# ESP_programmer_QFN_2.net
KiCad netlist of a schematic drawn in EAGLE
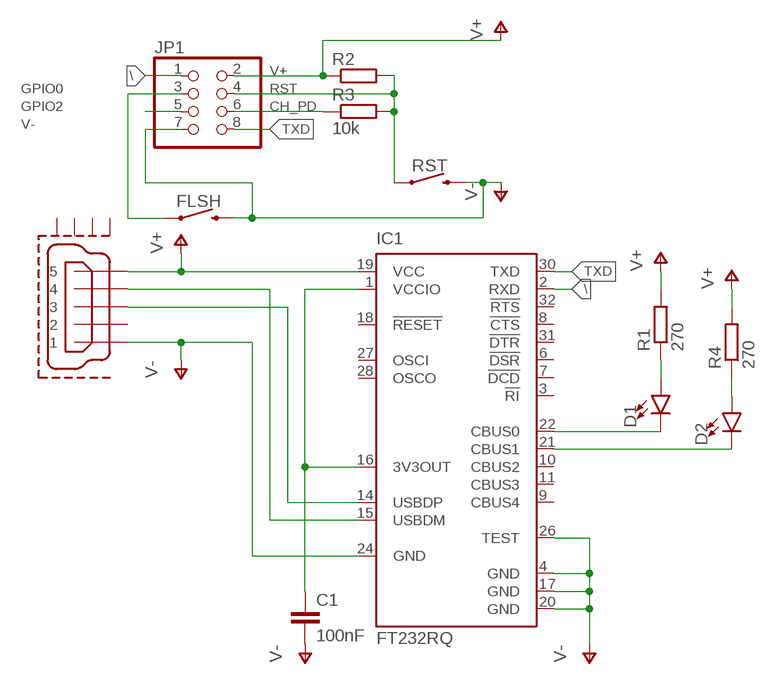
[diagram p0: schematic, sheet 1]

(export (version "E")
  (design (tool "Eeschema 10.0.6"))
  (components
    (comp (ref "C1")
      (value "100nF")
      (footprint "eagle-import:C1608")
      (libsource (lib "eagle-import") (part "C-EUC1608"))
    )
    (comp (ref "D1")
      (value "TX")
      (footprint "eagle-import:LED-0603")
      (libsource (lib "eagle-import") (part "LED-BLUE0603"))
    )
    (comp (ref "D2")
      (value "RX")
      (footprint "eagle-import:LED-0603")
      (libsource (lib "eagle-import") (part "LED-BLUE0603"))
    )
    (comp (ref "FLSH")
      (value "MOMENTARY-SWITCH-SPST-SMD-5.2-REDUNDANT")
      (footprint "eagle-import:TACTILE_SWITCH_SMD_5.2MM")
      (libsource (lib "eagle-import") (part "MOMENTARY-SWITCH-SPST-SMD-5.2-REDUNDANT"))
    )
    (comp (ref "IC1")
      (value "FT232RQ")
      (footprint "eagle-import:QFN32")
      (libsource (lib "eagle-import") (part "FT232RQ"))
    )
    (comp (ref "JP1")
      (value "PINHD-2X4")
      (footprint "eagle-import:2X04")
      (libsource (lib "eagle-import") (part "PINHD-2X4"))
    )
    (comp (ref "R1")
      (value "270")
      (footprint "eagle-import:R2012")
      (libsource (lib "eagle-import") (part "RR2012"))
    )
    (comp (ref "R2")
      (value "10k")
      (footprint "eagle-import:R2012")
      (libsource (lib "eagle-import") (part "RR2012"))
    )
    (comp (ref "R3")
      (value "10k")
      (footprint "eagle-import:R2012")
      (libsource (lib "eagle-import") (part "RR2012"))
    )
    (comp (ref "R4")
      (value "270")
      (footprint "eagle-import:R2012")
      (libsource (lib "eagle-import") (part "RR2012"))
    )
    (comp (ref "RST")
      (value "MOMENTARY-SWITCH-SPST-SMD-5.2-REDUNDANT")
      (footprint "eagle-import:TACTILE_SWITCH_SMD_5.2MM")
      (libsource (lib "eagle-import") (part "MOMENTARY-SWITCH-SPST-SMD-5.2-REDUNDANT"))
    )
    (comp (ref "U1")
      (value "MICRO-USB-RECEPTACLE47589-0001")
      (footprint "eagle-import:47589-0001")
      (libsource (lib "eagle-import") (part "MICRO-USB-RECEPTACLE47589-0001"))
    )
  )
  (nets
    (net (code "1") (name "/CH_PD") (class "Default")
      (node (ref "JP1") (pin "6") (pinfunction "6_6") (pintype "passive"))
      (node (ref "R3") (pin "1") (pinfunction "1_1") (pintype "passive"))
    )
    (net (code "2") (name "/GPIO0") (class "Default")
      (node (ref "FLSH") (pin "1") (pinfunction "1_1") (pintype "passive"))
      (node (ref "FLSH") (pin "2") (pinfunction "1_2") (pintype "passive"))
      (node (ref "JP1") (pin "3") (pinfunction "3_3") (pintype "passive"))
    )
    (net (code "3") (name "/GPIO2") (class "Default")
      (node (ref "JP1") (pin "5") (pinfunction "5_5") (pintype "passive"))
    )
    (net (code "4") (name "/RST") (class "Default")
      (node (ref "JP1") (pin "4") (pinfunction "4_4") (pintype "passive"))
      (node (ref "R2") (pin "2") (pinfunction "2_2") (pintype "passive"))
      (node (ref "R3") (pin "2") (pinfunction "2_2") (pintype "passive"))
      (node (ref "RST") (pin "1") (pinfunction "1_1") (pintype "passive"))
      (node (ref "RST") (pin "2") (pinfunction "1_2") (pintype "passive"))
    )
    (net (code "5") (name "Net-(D1-PadA)") (class "Default")
      (node (ref "D1") (pin "A") (pinfunction "A_A") (pintype "passive"))
      (node (ref "R1") (pin "1") (pinfunction "1_1") (pintype "passive"))
    )
    (net (code "6") (name "Net-(D2-PadA)") (class "Default")
      (node (ref "D2") (pin "A") (pinfunction "A_A") (pintype "passive"))
      (node (ref "R4") (pin "1") (pinfunction "1_1") (pintype "passive"))
    )
    (net (code "7") (name "Net-(IC1-3V3OUT)") (class "Default")
      (node (ref "C1") (pin "1") (pinfunction "1_1") (pintype "passive"))
      (node (ref "IC1") (pin "1") (pinfunction "VCCIO_1") (pintype "power_in"))
      (node (ref "IC1") (pin "16") (pinfunction "3V3OUT_16") (pintype "output"))
    )
    (net (code "8") (name "Net-(IC1-CBUS0)") (class "Default")
      (node (ref "D1") (pin "C") (pinfunction "C_C") (pintype "passive"))
      (node (ref "IC1") (pin "22") (pinfunction "CBUS0_22") (pintype "bidirectional"))
    )
    (net (code "9") (name "Net-(IC1-CBUS1)") (class "Default")
      (node (ref "D2") (pin "C") (pinfunction "C_C") (pintype "passive"))
      (node (ref "IC1") (pin "21") (pinfunction "CBUS1_21") (pintype "bidirectional"))
    )
    (net (code "10") (name "Net-(IC1-USBDM)") (class "Default")
      (node (ref "IC1") (pin "15") (pinfunction "USBDM_15") (pintype "bidirectional"))
      (node (ref "U1") (pin "4") (pinfunction "4_4") (pintype "input"))
    )
    (net (code "11") (name "Net-(IC1-USBDP)") (class "Default")
      (node (ref "IC1") (pin "14") (pinfunction "USBDP_14") (pintype "bidirectional"))
      (node (ref "U1") (pin "3") (pinfunction "3_3") (pintype "input"))
    )
    (net (code "12") (name "TXD") (class "Default")
      (node (ref "IC1") (pin "30") (pinfunction "TXD_30") (pintype "output"))
      (node (ref "JP1") (pin "8") (pinfunction "8_8") (pintype "passive"))
    )
    (net (code "13") (name "V+") (class "Default")
      (node (ref "IC1") (pin "19") (pinfunction "VCC_19") (pintype "power_in"))
      (node (ref "JP1") (pin "2") (pinfunction "2_2") (pintype "passive"))
      (node (ref "R1") (pin "2") (pinfunction "2_2") (pintype "passive"))
      (node (ref "R2") (pin "1") (pinfunction "1_1") (pintype "passive"))
      (node (ref "R4") (pin "2") (pinfunction "2_2") (pintype "passive"))
      (node (ref "U1") (pin "5") (pinfunction "5_5") (pintype "input"))
    )
    (net (code "14") (name "V-") (class "Default")
      (node (ref "C1") (pin "2") (pinfunction "2_2") (pintype "passive"))
      (node (ref "FLSH") (pin "3") (pinfunction "2_3") (pintype "passive"))
      (node (ref "FLSH") (pin "4") (pinfunction "2_4") (pintype "passive"))
      (node (ref "IC1") (pin "17") (pinfunction "GND_17") (pintype "power_in"))
      (node (ref "IC1") (pin "20") (pinfunction "GND_20") (pintype "power_in"))
      (node (ref "IC1") (pin "24") (pinfunction "GND_24") (pintype "power_in"))
      (node (ref "IC1") (pin "26") (pinfunction "TEST_26") (pintype "input"))
      (node (ref "IC1") (pin "4") (pinfunction "GND_4") (pintype "power_in"))
      (node (ref "JP1") (pin "7") (pinfunction "7_7") (pintype "passive"))
      (node (ref "RST") (pin "3") (pinfunction "2_3") (pintype "passive"))
      (node (ref "RST") (pin "4") (pinfunction "2_4") (pintype "passive"))
      (node (ref "U1") (pin "1") (pinfunction "1_1") (pintype "input"))
    )
    (net (code "15") (name "\\") (class "Default")
      (node (ref "IC1") (pin "2") (pinfunction "RXD_2") (pintype "input"))
      (node (ref "JP1") (pin "1") (pinfunction "1_1") (pintype "passive"))
    )
    (net (code "16") (name "unconnected-(IC1-CBUS2-Pad10)") (class "Default")
      (node (ref "IC1") (pin "10") (pinfunction "CBUS2_10") (pintype "bidirectional"))
    )
    (net (code "17") (name "unconnected-(IC1-CBUS3-Pad11)") (class "Default")
      (node (ref "IC1") (pin "11") (pinfunction "CBUS3_11") (pintype "bidirectional"))
    )
    (net (code "18") (name "unconnected-(IC1-CBUS4-Pad9)") (class "Default")
      (node (ref "IC1") (pin "9") (pinfunction "CBUS4_9") (pintype "bidirectional"))
    )
    (net (code "19") (name "unconnected-(IC1-OSCI-Pad27)") (class "Default")
      (node (ref "IC1") (pin "27") (pinfunction "OSCI_27") (pintype "input"))
    )
    (net (code "20") (name "unconnected-(IC1-OSCO-Pad28)") (class "Default")
      (node (ref "IC1") (pin "28") (pinfunction "OSCO_28") (pintype "output"))
    )
    (net (code "21") (name "unconnected-(IC1-~{CTS}-Pad8)") (class "Default")
      (node (ref "IC1") (pin "8") (pinfunction "~{CTS}_8") (pintype "input"))
    )
    (net (code "22") (name "unconnected-(IC1-~{DCD}-Pad7)") (class "Default")
      (node (ref "IC1") (pin "7") (pinfunction "~{DCD}_7") (pintype "input"))
    )
    (net (code "23") (name "unconnected-(IC1-~{DSR}-Pad6)") (class "Default")
      (node (ref "IC1") (pin "6") (pinfunction "~{DSR}_6") (pintype "input"))
    )
    (net (code "24") (name "unconnected-(IC1-~{DTR}-Pad31)") (class "Default")
      (node (ref "IC1") (pin "31") (pinfunction "~{DTR}_31") (pintype "output"))
    )
    (net (code "25") (name "unconnected-(IC1-~{RESET}-Pad18)") (class "Default")
      (node (ref "IC1") (pin "18") (pinfunction "~{RESET}_18") (pintype "input"))
    )
    (net (code "26") (name "unconnected-(IC1-~{RI}-Pad3)") (class "Default")
      (node (ref "IC1") (pin "3") (pinfunction "~{RI}_3") (pintype "input"))
    )
    (net (code "27") (name "unconnected-(IC1-~{RTS}-Pad32)") (class "Default")
      (node (ref "IC1") (pin "32") (pinfunction "~{RTS}_32") (pintype "output"))
    )
    (net (code "28") (name "unconnected-(U1-GND1-PadCASING1)") (class "Default")
      (node (ref "U1") (pin "CASING1") (pinfunction "GND1_CASING1") (pintype "bidirectional"))
    )
    (net (code "29") (name "unconnected-(U1-GND2-PadCASING2)") (class "Default")
      (node (ref "U1") (pin "CASING2") (pinfunction "GND2_CASING2") (pintype "bidirectional"))
    )
    (net (code "30") (name "unconnected-(U1-GND3-PadCASING3)") (class "Default")
      (node (ref "U1") (pin "CASING3") (pinfunction "GND3_CASING3") (pintype "bidirectional"))
    )
    (net (code "31") (name "unconnected-(U1-GND4-PadCASING4)") (class "Default")
      (node (ref "U1") (pin "CASING4") (pinfunction "GND4_CASING4") (pintype "bidirectional"))
    )
    (net (code "32") (name "unconnected-(U1-Pad2)") (class "Default")
      (node (ref "U1") (pin "2") (pinfunction "2_2") (pintype "input"))
    )
  )
)
